# power2V5.net
KiCad netlist of a schematic drawn in Altium Designer
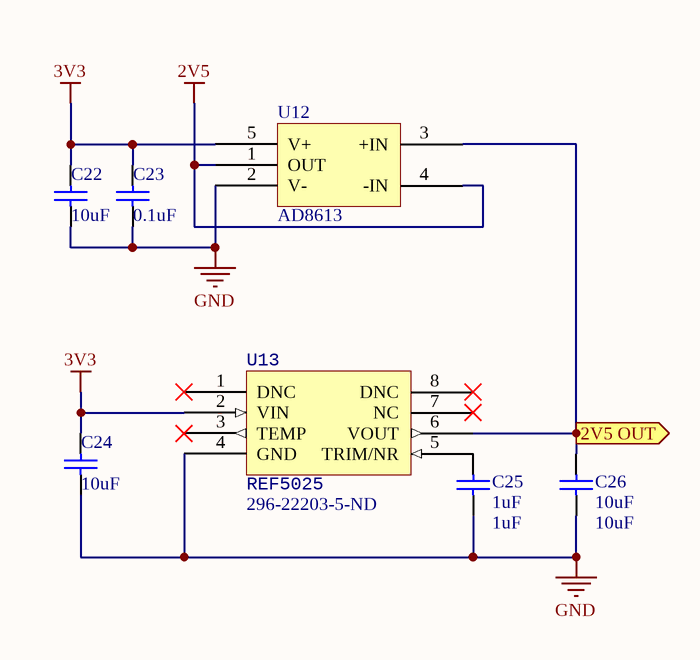
[diagram p0: power2V5.SchDoc]

(export (version "E")
  (design (tool "Eeschema 10.0.6"))
  (components
    (comp (ref "C22")
      (value "10uF")
      (footprint "1608[0603]")
      (description "Capacitor (Semiconductor SIM Model)")
      (fields (field (name "PUBLISHER") "Altium Limited"))
      (libsource (lib "Miscellaneous Devices") (part "Cap Semi"))
    )
    (comp (ref "C23")
      (value "0.1uF")
      (footprint "1608[0603]")
      (description "Capacitor (Semiconductor SIM Model)")
      (fields (field (name "PUBLISHER") "Altium Limited"))
      (libsource (lib "Miscellaneous Devices") (part "Cap Semi"))
    )
    (comp (ref "C24")
      (value "10uF")
      (footprint "1608[0603]")
      (description "Capacitor (Semiconductor SIM Model)")
      (fields (field (name "PUBLISHER") "Altium Limited"))
      (libsource (lib "Miscellaneous Devices") (part "Cap Semi"))
    )
    (comp (ref "C25")
      (value "1uF")
      (footprint "1608[0603]")
      (description "Capacitor (Semiconductor SIM Model)")
      (fields (field (name "ALTIUM_VALUE") "1uF") (field (name "PUBLISHER") "Altium Limited"))
      (libsource (lib "Miscellaneous Devices") (part "Cap Semi"))
    )
    (comp (ref "C26")
      (value "10uF")
      (footprint "1608[0603]")
      (description "Capacitor (Semiconductor SIM Model)")
      (fields (field (name "ALTIUM_VALUE") "10uF") (field (name "PUBLISHER") "Altium Limited"))
      (libsource (lib "Miscellaneous Devices") (part "Cap Semi"))
    )
    (comp (ref "U12")
      (value "AD8613")
      (footprint "SOP-65P200X125-5N")
      (description "Low power, low noise rail-to-rail op-amp.")
      (libsource (lib "PAY") (part "AD8613"))
    )
    (comp (ref "U13")
      (value "REF5025")
      (footprint "SOIC127P500X600-8N")
      (description "Voltage Reference")
      (fields (field (name "SUPPLIER PART NUMBER 1") "296-22203-5-ND"))
      (libsource (lib "heron-general") (part "REF5025"))
    )
  )
  (nets
    (net (code "1") (name "/2V5 OUT") (class "Default")
      (node (ref "C26") (pin "2") (pinfunction "2_2") (pintype "passive"))
      (node (ref "U12") (pin "3") (pinfunction "+IN_3") (pintype "passive"))
      (node (ref "U13") (pin "6") (pinfunction "VOUT_6") (pintype "output"))
    )
    (net (code "2") (name "2V5") (class "Default")
      (node (ref "U12") (pin "1") (pinfunction "OUT_1") (pintype "passive"))
      (node (ref "U12") (pin "4") (pinfunction "-IN_4") (pintype "passive"))
    )
    (net (code "3") (name "3V3") (class "Default")
      (node (ref "C22") (pin "2") (pinfunction "2_2") (pintype "passive"))
      (node (ref "C23") (pin "2") (pinfunction "2_2") (pintype "passive"))
      (node (ref "C24") (pin "2") (pinfunction "2_2") (pintype "passive"))
      (node (ref "U12") (pin "5") (pinfunction "V+_5") (pintype "passive"))
      (node (ref "U13") (pin "2") (pinfunction "VIN_2") (pintype "input"))
    )
    (net (code "4") (name "GND") (class "Default")
      (node (ref "C22") (pin "1") (pinfunction "1_1") (pintype "passive"))
      (node (ref "C23") (pin "1") (pinfunction "1_1") (pintype "passive"))
      (node (ref "C24") (pin "1") (pinfunction "1_1") (pintype "passive"))
      (node (ref "C25") (pin "1") (pinfunction "1_1") (pintype "passive"))
      (node (ref "C26") (pin "1") (pinfunction "1_1") (pintype "passive"))
      (node (ref "U12") (pin "2") (pinfunction "V-_2") (pintype "passive"))
      (node (ref "U13") (pin "4") (pinfunction "GND_4") (pintype "power_in"))
    )
    (net (code "5") (name "Net-(U13-TRIM{slash}NR)") (class "Default")
      (node (ref "C25") (pin "2") (pinfunction "2_2") (pintype "passive"))
      (node (ref "U13") (pin "5") (pinfunction "TRIM/NR_5") (pintype "input"))
    )
    (net (code "6") (name "unconnected-(U13-DNC-Pad1)") (class "Default")
      (node (ref "U13") (pin "1") (pinfunction "DNC_1") (pintype "passive+no_connect"))
    )
    (net (code "7") (name "unconnected-(U13-DNC-Pad8)") (class "Default")
      (node (ref "U13") (pin "8") (pinfunction "DNC_8") (pintype "passive+no_connect"))
    )
    (net (code "8") (name "unconnected-(U13-NC-Pad7)") (class "Default")
      (node (ref "U13") (pin "7") (pinfunction "NC_7") (pintype "passive+no_connect"))
    )
    (net (code "9") (name "unconnected-(U13-TEMP-Pad3)") (class "Default")
      (node (ref "U13") (pin "3") (pinfunction "TEMP_3") (pintype "output+no_connect"))
    )
  )
)
